# motordriver.net
KiCad netlist of a schematic drawn in Altium Designer
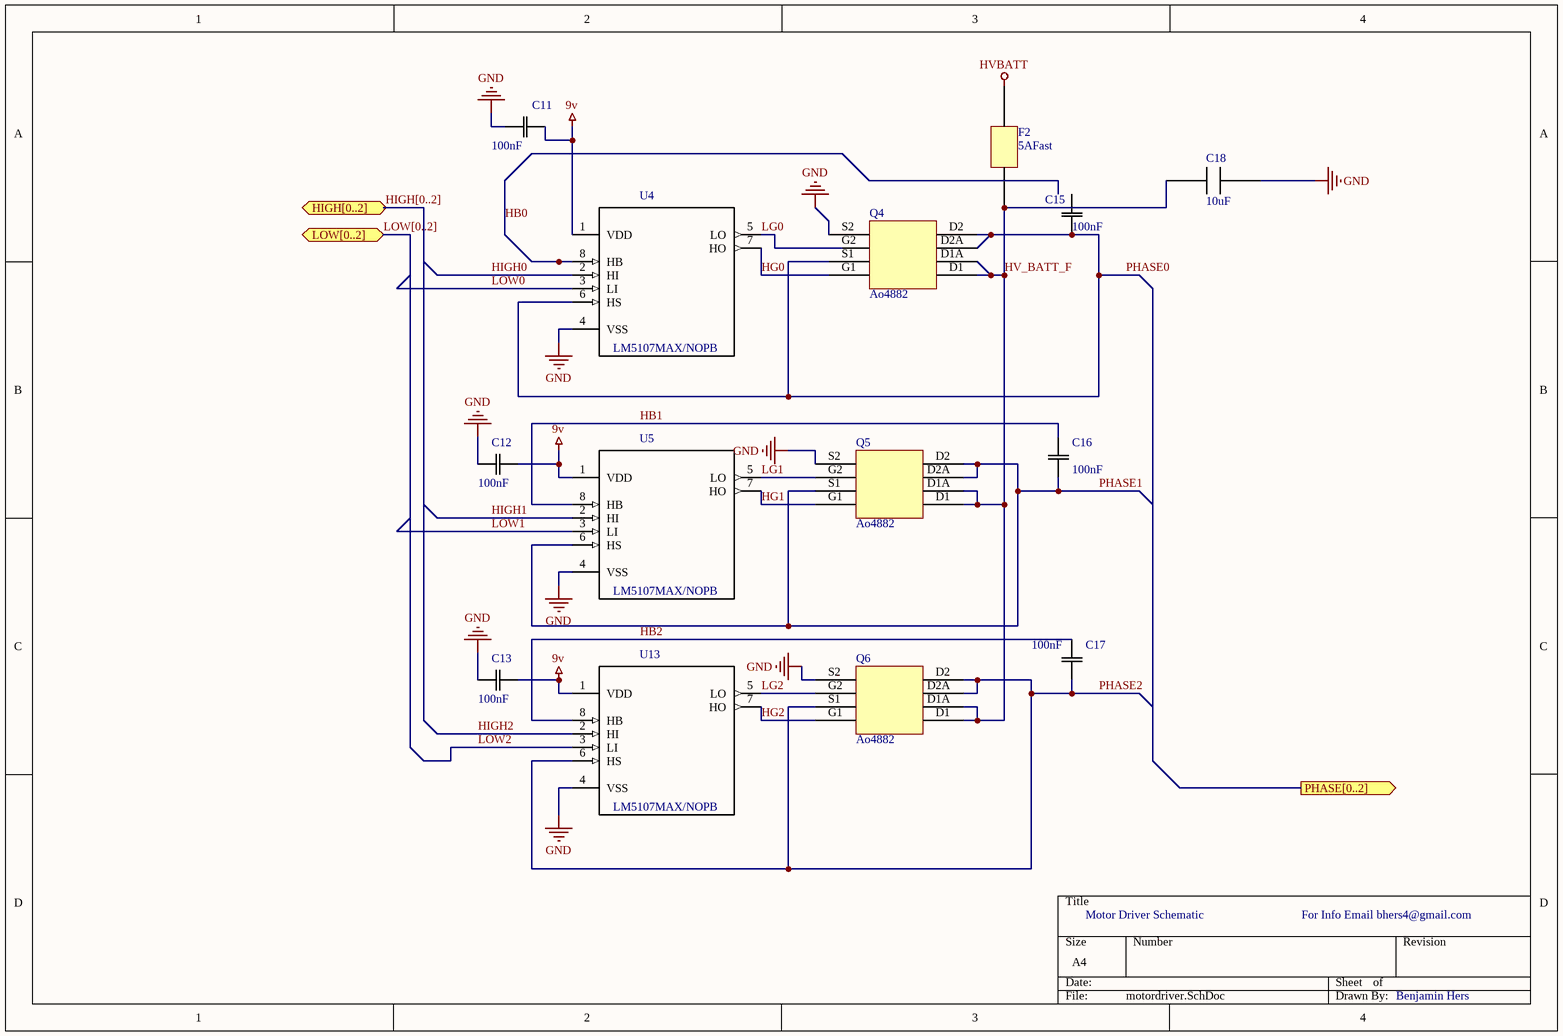
[diagram p0: motordriver.SchDoc]

(export (version "E")
  (design (tool "Eeschema 10.0.6"))
  (components
    (comp (ref "C11")
      (value "100nF")
      (footprint "CAPC2013X110N")
      (description "Capacitor; Ceramic; Cap; .100UF ; Tol+-10%; SMD; Vol-Rtg 50V; X7R, Tape/Reel")
      (fields (field (name "MP") "C0805C104K5RACTU") (field (name "MF") "Kemet"))
      (libsource (lib "100nF-C0805C104K5RACTU") (part "C0805C104K5RACTU"))
    )
    (comp (ref "C12")
      (value "100nF")
      (footprint "CAPC2013X110N")
      (description "Capacitor; Ceramic; Cap; .100UF ; Tol+-10%; SMD; Vol-Rtg 50V; X7R, Tape/Reel")
      (fields (field (name "MP") "C0805C104K5RACTU") (field (name "MF") "Kemet"))
      (libsource (lib "100nF-C0805C104K5RACTU") (part "C0805C104K5RACTU"))
    )
    (comp (ref "C13")
      (value "100nF")
      (footprint "CAPC2013X110N")
      (description "Capacitor; Ceramic; Cap; .100UF ; Tol+-10%; SMD; Vol-Rtg 50V; X7R, Tape/Reel")
      (fields (field (name "MP") "C0805C104K5RACTU") (field (name "MF") "Kemet"))
      (libsource (lib "100nF-C0805C104K5RACTU") (part "C0805C104K5RACTU"))
    )
    (comp (ref "C15")
      (value "100nF")
      (footprint "CAPC2013X110N")
      (description "Capacitor; Ceramic; Cap; .100UF ; Tol+-10%; SMD; Vol-Rtg 50V; X7R, Tape/Reel")
      (fields (field (name "MP") "C0805C104K5RACTU") (field (name "MF") "Kemet"))
      (libsource (lib "") (part "C0805C104K5RACTU_2"))
    )
    (comp (ref "C16")
      (value "100nF")
      (footprint "CAPC2013X110N")
      (description "Capacitor; Ceramic; Cap; .100UF ; Tol+-10%; SMD; Vol-Rtg 50V; X7R, Tape/Reel")
      (fields (field (name "MP") "C0805C104K5RACTU") (field (name "MF") "Kemet"))
      (libsource (lib "") (part "C0805C104K5RACTU_1"))
    )
    (comp (ref "C17")
      (value "100nF")
      (footprint "CAPC2013X110N")
      (description "Capacitor; Ceramic; Cap; .100UF ; Tol+-10%; SMD; Vol-Rtg 50V; X7R, Tape/Reel")
      (fields (field (name "MP") "C0805C104K5RACTU") (field (name "MF") "Kemet"))
      (libsource (lib "") (part "C0805C104K5RACTU_1"))
    )
    (comp (ref "C18")
      (value "10uF")
      (footprint "CAPC3216X100N")
      (libsource (lib "10uFCAPC3216X100N") (part "Component_1"))
    )
    (comp (ref "F2") (value "5AFast") (footprint "1206") (libsource (lib "Fuse1206") (part "5AFast1206")))
    (comp (ref "Q4")
      (value "Ao4882")
      (footprint "SOIC127P490X600X175-8N")
      (libsource (lib "Ao4882") (part "Ao4882"))
    )
    (comp (ref "Q5")
      (value "Ao4882")
      (footprint "SOIC127P490X600X175-8N")
      (libsource (lib "Ao4882") (part "Ao4882"))
    )
    (comp (ref "Q6")
      (value "Ao4882")
      (footprint "SOIC127P490X600X175-8N")
      (libsource (lib "Ao4882") (part "Ao4882"))
    )
    (comp (ref "U4")
      (value "LM5107MAX/NOPB")
      (footprint "SOIC127P620X175-8N")
      (description "MOSFET DRVR 1.4A 2-OUT Hi/Lo Side Full Brdg/Half Brdg Non-Inv 8-Pin SOIC N T/R")
      (fields
        (field (name "DIGI-KEY_PART_NUMBER") "LM5107MAX/NOPBCT-ND")
        (field (name "MF") "Texas Instruments")
      )
      (libsource (lib "LM5107MAX_NOPB") (part "LM5107MAX/NOPB"))
    )
    (comp (ref "U5")
      (value "LM5107MAX/NOPB")
      (footprint "SOIC127P620X175-8N")
      (description "MOSFET DRVR 1.4A 2-OUT Hi/Lo Side Full Brdg/Half Brdg Non-Inv 8-Pin SOIC N T/R")
      (fields
        (field (name "DIGI-KEY_PART_NUMBER") "LM5107MAX/NOPBCT-ND")
        (field (name "MF") "Texas Instruments")
      )
      (libsource (lib "LM5107MAX_NOPB") (part "LM5107MAX/NOPB"))
    )
    (comp (ref "U13")
      (value "LM5107MAX/NOPB")
      (footprint "SOIC127P620X175-8N")
      (description "MOSFET DRVR 1.4A 2-OUT Hi/Lo Side Full Brdg/Half Brdg Non-Inv 8-Pin SOIC N T/R")
      (fields
        (field (name "DIGI-KEY_PART_NUMBER") "LM5107MAX/NOPBCT-ND")
        (field (name "MF") "Texas Instruments")
      )
      (libsource (lib "LM5107MAX_NOPB") (part "LM5107MAX/NOPB"))
    )
  )
  (nets
    (net (code "1") (name "/HB0") (class "Default")
      (node (ref "U4") (pin "8") (pinfunction "HB_8") (pintype "input"))
    )
    (net (code "2") (name "/HB1") (class "Default")
      (node (ref "C16") (pin "1") (pinfunction "C1_1") (pintype "passive"))
      (node (ref "U5") (pin "8") (pinfunction "HB_8") (pintype "input"))
    )
    (net (code "3") (name "/HB2") (class "Default")
      (node (ref "C17") (pin "1") (pinfunction "C1_1") (pintype "passive"))
      (node (ref "U13") (pin "8") (pinfunction "HB_8") (pintype "input"))
    )
    (net (code "4") (name "/HG0") (class "Default")
      (node (ref "U4") (pin "7") (pinfunction "HO_7") (pintype "output"))
    )
    (net (code "5") (name "/HG1") (class "Default")
      (node (ref "U5") (pin "7") (pinfunction "HO_7") (pintype "output"))
    )
    (net (code "6") (name "/HG2") (class "Default")
      (node (ref "U13") (pin "7") (pinfunction "HO_7") (pintype "output"))
    )
    (net (code "7") (name "/HIGH0") (class "Default")
      (node (ref "U4") (pin "2") (pinfunction "HI_2") (pintype "input"))
    )
    (net (code "8") (name "/HIGH1") (class "Default")
      (node (ref "U5") (pin "2") (pinfunction "HI_2") (pintype "input"))
    )
    (net (code "9") (name "/HIGH2") (class "Default")
      (node (ref "U13") (pin "2") (pinfunction "HI_2") (pintype "input"))
    )
    (net (code "11") (name "/HV_BATT_F") (class "Default")
      (node (ref "F2") (pin "Fusein") (pinfunction "In_Fusein") (pintype "passive"))
    )
    (net (code "12") (name "/LG0") (class "Default")
      (node (ref "U4") (pin "5") (pinfunction "LO_5") (pintype "output"))
    )
    (net (code "13") (name "/LG1") (class "Default")
      (node (ref "U5") (pin "5") (pinfunction "LO_5") (pintype "output"))
    )
    (net (code "14") (name "/LG2") (class "Default")
      (node (ref "U13") (pin "5") (pinfunction "LO_5") (pintype "output"))
    )
    (net (code "15") (name "/LOW0") (class "Default")
      (node (ref "U4") (pin "3") (pinfunction "LI_3") (pintype "input"))
    )
    (net (code "16") (name "/LOW1") (class "Default")
      (node (ref "U5") (pin "3") (pinfunction "LI_3") (pintype "input"))
    )
    (net (code "17") (name "/LOW2") (class "Default")
      (node (ref "U13") (pin "3") (pinfunction "LI_3") (pintype "input"))
    )
    (net (code "19") (name "/PHASE0") (class "Default")
      (node (ref "C15") (pin "1") (pinfunction "C1_1") (pintype "passive"))
      (node (ref "U4") (pin "6") (pinfunction "HS_6") (pintype "input"))
    )
    (net (code "20") (name "/PHASE1") (class "Default")
      (node (ref "C16") (pin "2") (pinfunction "C2_2") (pintype "passive"))
      (node (ref "U5") (pin "6") (pinfunction "HS_6") (pintype "input"))
    )
    (net (code "21") (name "/PHASE2") (class "Default")
      (node (ref "C17") (pin "2") (pinfunction "C2_2") (pintype "passive"))
      (node (ref "U13") (pin "6") (pinfunction "HS_6") (pintype "input"))
    )
    (net (code "23") (name "9v") (class "Default")
      (node (ref "C11") (pin "1") (pinfunction "C1_1") (pintype "passive"))
      (node (ref "C12") (pin "2") (pinfunction "C2_2") (pintype "passive"))
      (node (ref "C13") (pin "2") (pinfunction "C2_2") (pintype "passive"))
      (node (ref "U13") (pin "1") (pinfunction "VDD_1") (pintype "power_in"))
      (node (ref "U4") (pin "1") (pinfunction "VDD_1") (pintype "power_in"))
      (node (ref "U5") (pin "1") (pinfunction "VDD_1") (pintype "power_in"))
    )
    (net (code "24") (name "GND") (class "Default")
      (node (ref "C11") (pin "2") (pinfunction "C2_2") (pintype "passive"))
      (node (ref "C12") (pin "1") (pinfunction "C1_1") (pintype "passive"))
      (node (ref "C13") (pin "1") (pinfunction "C1_1") (pintype "passive"))
      (node (ref "U13") (pin "4") (pinfunction "VSS_4") (pintype "power_in"))
      (node (ref "U4") (pin "4") (pinfunction "VSS_4") (pintype "power_in"))
      (node (ref "U5") (pin "4") (pinfunction "VSS_4") (pintype "power_in"))
    )
    (net (code "25") (name "HVBATT") (class "Default")
      (node (ref "F2") (pin "Fuseout") (pinfunction "Out_Fuseout") (pintype "passive"))
    )
    (net (code "26") (name "unconnected-(C15-C2-Pad2)") (class "Default")
      (node (ref "C15") (pin "2") (pinfunction "C2_2") (pintype "passive"))
    )
    (net (code "27") (name "unconnected-(C18-PadIn)") (class "Default")
      (node (ref "C18") (pin "In") (pinfunction "In_In") (pintype "passive"))
    )
    (net (code "28") (name "unconnected-(C18-PadOut)") (class "Default")
      (node (ref "C18") (pin "Out") (pinfunction "Out_Out") (pintype "passive"))
    )
    (net (code "29") (name "unconnected-(Q4-1-PadS2)") (class "Default")
      (node (ref "Q4") (pin "S2") (pinfunction "1_S2") (pintype "passive"))
    )
    (net (code "30") (name "unconnected-(Q4-2-PadG2)") (class "Default")
      (node (ref "Q4") (pin "G2") (pinfunction "2_G2") (pintype "passive"))
    )
    (net (code "31") (name "unconnected-(Q4-3-PadS1)") (class "Default")
      (node (ref "Q4") (pin "S1") (pinfunction "3_S1") (pintype "passive"))
    )
    (net (code "32") (name "unconnected-(Q4-4-PadG1)") (class "Default")
      (node (ref "Q4") (pin "G1") (pinfunction "4_G1") (pintype "passive"))
    )
    (net (code "33") (name "unconnected-(Q4-5-PadD1)") (class "Default")
      (node (ref "Q4") (pin "D1") (pinfunction "5_D1") (pintype "passive"))
    )
    (net (code "34") (name "unconnected-(Q4-6-PadD1A)") (class "Default")
      (node (ref "Q4") (pin "D1A") (pinfunction "6_D1A") (pintype "passive"))
    )
    (net (code "35") (name "unconnected-(Q4-7-PadD2A)") (class "Default")
      (node (ref "Q4") (pin "D2A") (pinfunction "7_D2A") (pintype "passive"))
    )
    (net (code "36") (name "unconnected-(Q4-8-PadD2)") (class "Default")
      (node (ref "Q4") (pin "D2") (pinfunction "8_D2") (pintype "passive"))
    )
    (net (code "37") (name "unconnected-(Q5-1-PadS2)") (class "Default")
      (node (ref "Q5") (pin "S2") (pinfunction "1_S2") (pintype "passive"))
    )
    (net (code "38") (name "unconnected-(Q5-2-PadG2)") (class "Default")
      (node (ref "Q5") (pin "G2") (pinfunction "2_G2") (pintype "passive"))
    )
    (net (code "39") (name "unconnected-(Q5-3-PadS1)") (class "Default")
      (node (ref "Q5") (pin "S1") (pinfunction "3_S1") (pintype "passive"))
    )
    (net (code "40") (name "unconnected-(Q5-4-PadG1)") (class "Default")
      (node (ref "Q5") (pin "G1") (pinfunction "4_G1") (pintype "passive"))
    )
    (net (code "41") (name "unconnected-(Q5-5-PadD1)") (class "Default")
      (node (ref "Q5") (pin "D1") (pinfunction "5_D1") (pintype "passive"))
    )
    (net (code "42") (name "unconnected-(Q5-6-PadD1A)") (class "Default")
      (node (ref "Q5") (pin "D1A") (pinfunction "6_D1A") (pintype "passive"))
    )
    (net (code "43") (name "unconnected-(Q5-7-PadD2A)") (class "Default")
      (node (ref "Q5") (pin "D2A") (pinfunction "7_D2A") (pintype "passive"))
    )
    (net (code "44") (name "unconnected-(Q5-8-PadD2)") (class "Default")
      (node (ref "Q5") (pin "D2") (pinfunction "8_D2") (pintype "passive"))
    )
    (net (code "45") (name "unconnected-(Q6-1-PadS2)") (class "Default")
      (node (ref "Q6") (pin "S2") (pinfunction "1_S2") (pintype "passive"))
    )
    (net (code "46") (name "unconnected-(Q6-2-PadG2)") (class "Default")
      (node (ref "Q6") (pin "G2") (pinfunction "2_G2") (pintype "passive"))
    )
    (net (code "47") (name "unconnected-(Q6-3-PadS1)") (class "Default")
      (node (ref "Q6") (pin "S1") (pinfunction "3_S1") (pintype "passive"))
    )
    (net (code "48") (name "unconnected-(Q6-4-PadG1)") (class "Default")
      (node (ref "Q6") (pin "G1") (pinfunction "4_G1") (pintype "passive"))
    )
    (net (code "49") (name "unconnected-(Q6-5-PadD1)") (class "Default")
      (node (ref "Q6") (pin "D1") (pinfunction "5_D1") (pintype "passive"))
    )
    (net (code "50") (name "unconnected-(Q6-6-PadD1A)") (class "Default")
      (node (ref "Q6") (pin "D1A") (pinfunction "6_D1A") (pintype "passive"))
    )
    (net (code "51") (name "unconnected-(Q6-7-PadD2A)") (class "Default")
      (node (ref "Q6") (pin "D2A") (pinfunction "7_D2A") (pintype "passive"))
    )
    (net (code "52") (name "unconnected-(Q6-8-PadD2)") (class "Default")
      (node (ref "Q6") (pin "D2") (pinfunction "8_D2") (pintype "passive"))
    )
  )
)
